# Display.net
KiCad netlist of a schematic drawn in Altium Designer
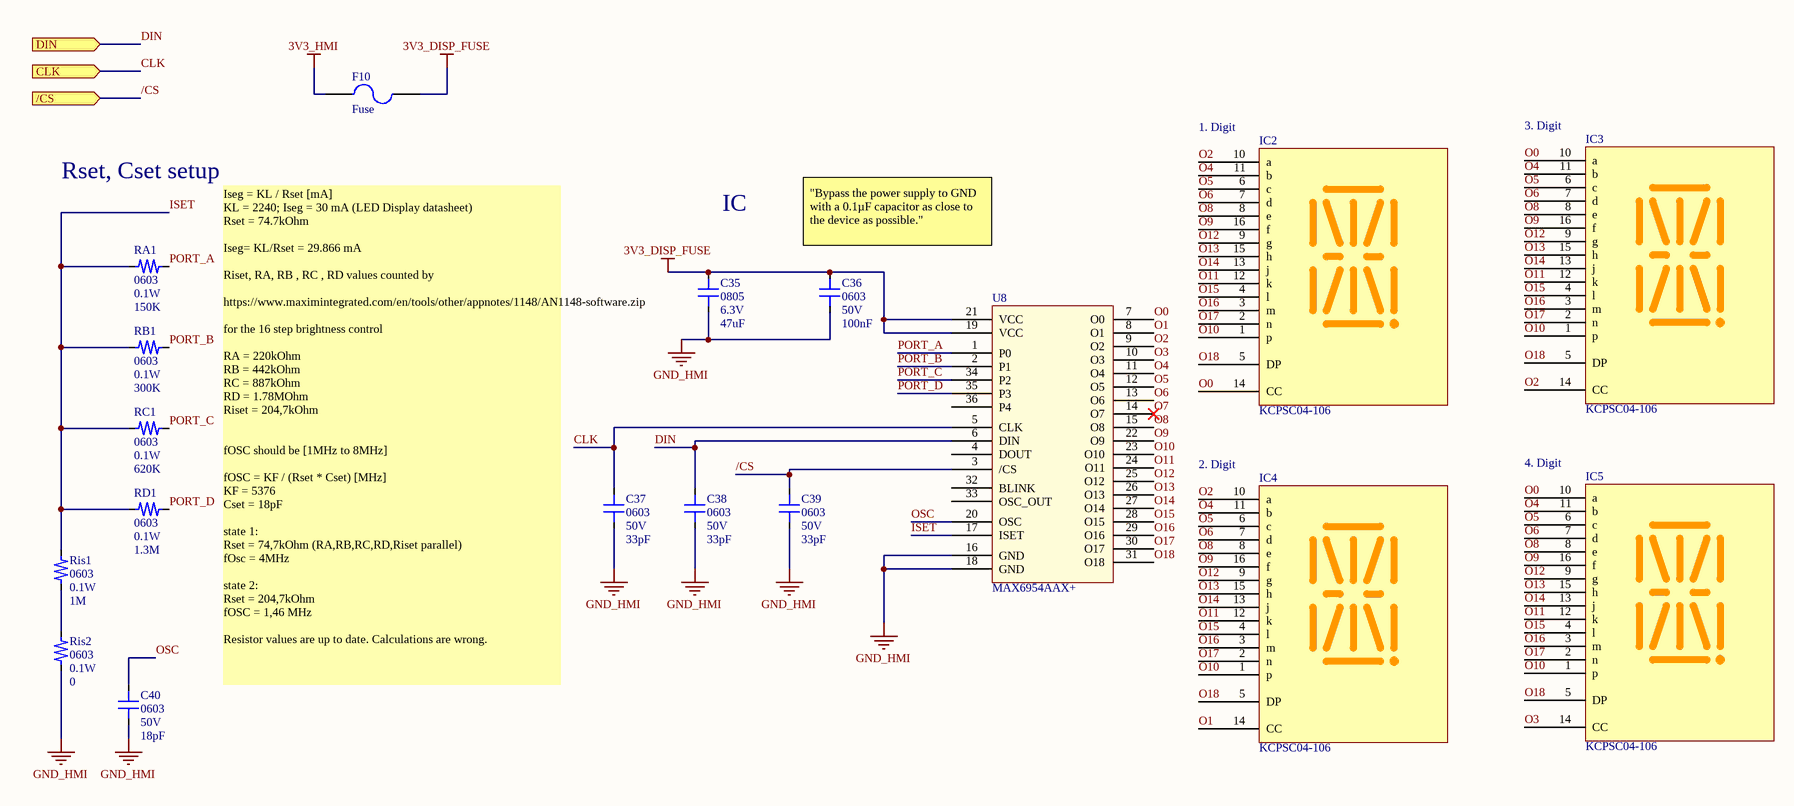
[diagram p0: Display.SchDoc]

(export (version "E")
  (design (tool "Eeschema 10.0.6"))
  (components
    (comp (ref "C35")
      (value "0805")
      (footprint "Components:C_0805")
      (fields
        (field (name "TOLERANCE") "20%")
        (field (name "PART NUMBER") "CL21A476MQYNNNE")
        (field (name "RATING") "6.3V")
        (field (name "ALTIUM_VALUE") "47uF")
      )
      (libsource (lib "Components") (part "Capacitor_Chip"))
    )
    (comp (ref "C36")
      (value "0603")
      (footprint "Components:C_0603")
      (fields
        (field (name "TOLERANCE") "10%")
        (field (name "PART NUMBER") "CC0603KRX7R9BB104")
        (field (name "RATING") "50V")
        (field (name "ALTIUM_VALUE") "100nF")
        (field (name "NI PART NUMBER") "716340-01")
      )
      (libsource (lib "Components") (part "Capacitor_Chip"))
    )
    (comp (ref "C37")
      (value "0603")
      (footprint "Components:C_0603")
      (fields
        (field (name "TOLERANCE") "5%")
        (field (name "PART NUMBER") "CL10C330JB8NNNC")
        (field (name "RATING") "50V")
        (field (name "ALTIUM_VALUE") "33pF")
        (field (name "NI PART NUMBER") "715511-01")
      )
      (libsource (lib "Components") (part "Capacitor_Chip"))
    )
    (comp (ref "C38")
      (value "0603")
      (footprint "Components:C_0603")
      (fields
        (field (name "TOLERANCE") "5%")
        (field (name "PART NUMBER") "CL10C330JB8NNNC")
        (field (name "RATING") "50V")
        (field (name "ALTIUM_VALUE") "33pF")
        (field (name "NI PART NUMBER") "715511-01")
      )
      (libsource (lib "Components") (part "Capacitor_Chip"))
    )
    (comp (ref "C39")
      (value "0603")
      (footprint "Components:C_0603")
      (fields
        (field (name "TOLERANCE") "5%")
        (field (name "PART NUMBER") "CL10C330JB8NNNC")
        (field (name "RATING") "50V")
        (field (name "ALTIUM_VALUE") "33pF")
        (field (name "NI PART NUMBER") "715511-01")
      )
      (libsource (lib "Components") (part "Capacitor_Chip"))
    )
    (comp (ref "C40")
      (value "0603")
      (footprint "Components:C_0603")
      (fields
        (field (name "TOLERANCE") "5%")
        (field (name "PART NUMBER") "CL10C180JB8NNNC")
        (field (name "RATING") "50V")
        (field (name "ALTIUM_VALUE") "18pF")
        (field (name "NI PART NUMBER") "715742-01")
      )
      (libsource (lib "Components") (part "Capacitor_Chip"))
    )
    (comp (ref "F10")
      (value "Fuse")
      (footprint "Components:F_0603")
      (fields (field (name "PART NUMBER") "0438001.WR") (field (name "NI PART NUMBER") "766308-01"))
      (libsource (lib "Components") (part "Fuse"))
    )
    (comp (ref "IC2")
      (value "KCPSC04-106")
      (footprint "Components:KCPSC04-106")
      (description "14SegmentDisplaySingle")
      (libsource (lib "KCPDC04_106") (part "14SegmentDisplaySingle"))
    )
    (comp (ref "IC3")
      (value "KCPSC04-106")
      (footprint "Components:KCPSC04-106")
      (description "14SegmentDisplaySingle")
      (libsource (lib "KCPDC04_106") (part "14SegmentDisplaySingle"))
    )
    (comp (ref "IC4")
      (value "KCPSC04-106")
      (footprint "Components:KCPSC04-106")
      (description "14SegmentDisplaySingle")
      (libsource (lib "KCPDC04_106") (part "14SegmentDisplaySingle"))
    )
    (comp (ref "IC5")
      (value "KCPSC04-106")
      (footprint "Components:KCPSC04-106")
      (description "14SegmentDisplaySingle")
      (libsource (lib "KCPDC04_106") (part "14SegmentDisplaySingle"))
    )
    (comp (ref "RA1")
      (value "0603")
      (footprint "Components:R_0603")
      (fields
        (field (name "TOLERANCE") "1%")
        (field (name "PART NUMBER") "CR-03FL7--220K")
        (field (name "RATING") "0.1W")
        (field (name "ALTIUM_VALUE") "150K")
        (field (name "NI PART NUMBER") "612705-01")
      )
      (libsource (lib "Components") (part "Resistor_Chip"))
    )
    (comp (ref "RB1")
      (value "0603")
      (footprint "Components:R_0603")
      (fields
        (field (name "TOLERANCE") "1%")
        (field (name "PART NUMBER") "CR-03FL7--220K")
        (field (name "RATING") "0.1W")
        (field (name "ALTIUM_VALUE") "300K")
        (field (name "NI PART NUMBER") "612705-01")
      )
      (libsource (lib "Components") (part "Resistor_Chip"))
    )
    (comp (ref "RC1")
      (value "0603")
      (footprint "Components:R_0603")
      (fields
        (field (name "TOLERANCE") "1%")
        (field (name "PART NUMBER") "CR-03FL7--220K")
        (field (name "RATING") "0.1W")
        (field (name "ALTIUM_VALUE") "620K")
        (field (name "NI PART NUMBER") "612705-01")
      )
      (libsource (lib "Components") (part "Resistor_Chip"))
    )
    (comp (ref "RD1")
      (value "0603")
      (footprint "Components:R_0603")
      (fields
        (field (name "TOLERANCE") "1%")
        (field (name "PART NUMBER") "CR-03FL7--220K")
        (field (name "RATING") "0.1W")
        (field (name "ALTIUM_VALUE") "1.3M")
        (field (name "NI PART NUMBER") "612705-01")
      )
      (libsource (lib "Components") (part "Resistor_Chip"))
    )
    (comp (ref "Ris1")
      (value "0603")
      (footprint "Components:R_0603")
      (fields
        (field (name "TOLERANCE") "1%")
        (field (name "PART NUMBER") "CR-03FL7---4K7")
        (field (name "RATING") "0.1W")
        (field (name "ALTIUM_VALUE") "1M")
        (field (name "NI PART NUMBER") "713782-01")
      )
      (libsource (lib "") (part "Resistor_Chip_1"))
    )
    (comp (ref "Ris2")
      (value "0603")
      (footprint "Components:R_0603")
      (fields
        (field (name "TOLERANCE") "1%")
        (field (name "PART NUMBER") "CR-03FL7--200K")
        (field (name "RATING") "0.1W")
        (field (name "ALTIUM_VALUE") "0")
        (field (name "NI PART NUMBER") "713614-01")
      )
      (libsource (lib "") (part "Resistor_Chip_1"))
    )
    (comp (ref "U8")
      (value "MAX6954AAX+")
      (footprint "Components:TSSOP-36")
      (description "16 Segment LED Driver")
      (libsource (lib "Components") (part "MAX6954"))
    )
  )
  (nets
    (net (code "1") (name "/CLK") (class "Default")
      (node (ref "C37") (pin "2") (pinfunction "C2_2") (pintype "passive"))
      (node (ref "U8") (pin "5") (pinfunction "CLK_5") (pintype "passive"))
    )
    (net (code "2") (name "/DIN") (class "Default")
      (node (ref "C38") (pin "2") (pinfunction "C2_2") (pintype "passive"))
      (node (ref "U8") (pin "6") (pinfunction "DIN_6") (pintype "passive"))
    )
    (net (code "3") (name "/ISET") (class "Default")
      (node (ref "RA1") (pin "2") (pinfunction "R2_2") (pintype "passive"))
      (node (ref "RB1") (pin "2") (pinfunction "R2_2") (pintype "passive"))
      (node (ref "RC1") (pin "2") (pinfunction "R2_2") (pintype "passive"))
      (node (ref "RD1") (pin "2") (pinfunction "R2_2") (pintype "passive"))
      (node (ref "Ris1") (pin "2") (pinfunction "R2_2") (pintype "passive"))
      (node (ref "U8") (pin "17") (pinfunction "ISET_17") (pintype "passive"))
    )
    (net (code "4") (name "/O0") (class "Default")
      (node (ref "IC2") (pin "14") (pinfunction "CC_14") (pintype "passive"))
      (node (ref "IC3") (pin "10") (pinfunction "a_10") (pintype "passive"))
      (node (ref "IC5") (pin "10") (pinfunction "a_10") (pintype "passive"))
      (node (ref "U8") (pin "7") (pinfunction "O0_7") (pintype "passive"))
    )
    (net (code "5") (name "/O1") (class "Default")
      (node (ref "IC4") (pin "14") (pinfunction "CC_14") (pintype "passive"))
      (node (ref "U8") (pin "8") (pinfunction "O1_8") (pintype "passive"))
    )
    (net (code "6") (name "/O2") (class "Default")
      (node (ref "IC2") (pin "10") (pinfunction "a_10") (pintype "passive"))
      (node (ref "IC3") (pin "14") (pinfunction "CC_14") (pintype "passive"))
      (node (ref "IC4") (pin "10") (pinfunction "a_10") (pintype "passive"))
      (node (ref "U8") (pin "9") (pinfunction "O2_9") (pintype "passive"))
    )
    (net (code "7") (name "/O3") (class "Default")
      (node (ref "IC5") (pin "14") (pinfunction "CC_14") (pintype "passive"))
      (node (ref "U8") (pin "10") (pinfunction "O3_10") (pintype "passive"))
    )
    (net (code "8") (name "/O4") (class "Default")
      (node (ref "IC2") (pin "11") (pinfunction "b_11") (pintype "passive"))
      (node (ref "IC3") (pin "11") (pinfunction "b_11") (pintype "passive"))
      (node (ref "IC4") (pin "11") (pinfunction "b_11") (pintype "passive"))
      (node (ref "IC5") (pin "11") (pinfunction "b_11") (pintype "passive"))
      (node (ref "U8") (pin "11") (pinfunction "O4_11") (pintype "passive"))
    )
    (net (code "9") (name "/O5") (class "Default")
      (node (ref "IC2") (pin "6") (pinfunction "c_6") (pintype "passive"))
      (node (ref "IC3") (pin "6") (pinfunction "c_6") (pintype "passive"))
      (node (ref "IC4") (pin "6") (pinfunction "c_6") (pintype "passive"))
      (node (ref "IC5") (pin "6") (pinfunction "c_6") (pintype "passive"))
      (node (ref "U8") (pin "12") (pinfunction "O5_12") (pintype "passive"))
    )
    (net (code "10") (name "/O6") (class "Default")
      (node (ref "IC2") (pin "7") (pinfunction "d_7") (pintype "passive"))
      (node (ref "IC3") (pin "7") (pinfunction "d_7") (pintype "passive"))
      (node (ref "IC4") (pin "7") (pinfunction "d_7") (pintype "passive"))
      (node (ref "IC5") (pin "7") (pinfunction "d_7") (pintype "passive"))
      (node (ref "U8") (pin "13") (pinfunction "O6_13") (pintype "passive"))
    )
    (net (code "11") (name "/O7") (class "Default")
      (node (ref "U8") (pin "14") (pinfunction "O7_14") (pintype "passive+no_connect"))
    )
    (net (code "12") (name "/O8") (class "Default")
      (node (ref "IC2") (pin "8") (pinfunction "e_8") (pintype "passive"))
      (node (ref "IC3") (pin "8") (pinfunction "e_8") (pintype "passive"))
      (node (ref "IC4") (pin "8") (pinfunction "e_8") (pintype "passive"))
      (node (ref "IC5") (pin "8") (pinfunction "e_8") (pintype "passive"))
      (node (ref "U8") (pin "15") (pinfunction "O8_15") (pintype "passive"))
    )
    (net (code "13") (name "/O9") (class "Default")
      (node (ref "IC2") (pin "16") (pinfunction "f_16") (pintype "passive"))
      (node (ref "IC3") (pin "16") (pinfunction "f_16") (pintype "passive"))
      (node (ref "IC4") (pin "16") (pinfunction "f_16") (pintype "passive"))
      (node (ref "IC5") (pin "16") (pinfunction "f_16") (pintype "passive"))
      (node (ref "U8") (pin "22") (pinfunction "O9_22") (pintype "passive"))
    )
    (net (code "14") (name "/O10") (class "Default")
      (node (ref "IC2") (pin "1") (pinfunction "p_1") (pintype "passive"))
      (node (ref "IC3") (pin "1") (pinfunction "p_1") (pintype "passive"))
      (node (ref "IC4") (pin "1") (pinfunction "p_1") (pintype "passive"))
      (node (ref "IC5") (pin "1") (pinfunction "p_1") (pintype "passive"))
      (node (ref "U8") (pin "23") (pinfunction "O10_23") (pintype "passive"))
    )
    (net (code "15") (name "/O11") (class "Default")
      (node (ref "IC2") (pin "12") (pinfunction "k_12") (pintype "passive"))
      (node (ref "IC3") (pin "12") (pinfunction "k_12") (pintype "passive"))
      (node (ref "IC4") (pin "12") (pinfunction "k_12") (pintype "passive"))
      (node (ref "IC5") (pin "12") (pinfunction "k_12") (pintype "passive"))
      (node (ref "U8") (pin "24") (pinfunction "O11_24") (pintype "passive"))
    )
    (net (code "16") (name "/O12") (class "Default")
      (node (ref "IC2") (pin "9") (pinfunction "g_9") (pintype "passive"))
      (node (ref "IC3") (pin "9") (pinfunction "g_9") (pintype "passive"))
      (node (ref "IC4") (pin "9") (pinfunction "g_9") (pintype "passive"))
      (node (ref "IC5") (pin "9") (pinfunction "g_9") (pintype "passive"))
      (node (ref "U8") (pin "25") (pinfunction "O12_25") (pintype "passive"))
    )
    (net (code "17") (name "/O13") (class "Default")
      (node (ref "IC2") (pin "15") (pinfunction "h_15") (pintype "passive"))
      (node (ref "IC3") (pin "15") (pinfunction "h_15") (pintype "passive"))
      (node (ref "IC4") (pin "15") (pinfunction "h_15") (pintype "passive"))
      (node (ref "IC5") (pin "15") (pinfunction "h_15") (pintype "passive"))
      (node (ref "U8") (pin "26") (pinfunction "O13_26") (pintype "passive"))
    )
    (net (code "18") (name "/O14") (class "Default")
      (node (ref "IC2") (pin "13") (pinfunction "j_13") (pintype "passive"))
      (node (ref "IC3") (pin "13") (pinfunction "j_13") (pintype "passive"))
      (node (ref "IC4") (pin "13") (pinfunction "j_13") (pintype "passive"))
      (node (ref "IC5") (pin "13") (pinfunction "j_13") (pintype "passive"))
      (node (ref "U8") (pin "27") (pinfunction "O14_27") (pintype "passive"))
    )
    (net (code "19") (name "/O15") (class "Default")
      (node (ref "IC2") (pin "4") (pinfunction "l_4") (pintype "passive"))
      (node (ref "IC3") (pin "4") (pinfunction "l_4") (pintype "passive"))
      (node (ref "IC4") (pin "4") (pinfunction "l_4") (pintype "passive"))
      (node (ref "IC5") (pin "4") (pinfunction "l_4") (pintype "passive"))
      (node (ref "U8") (pin "28") (pinfunction "O15_28") (pintype "passive"))
    )
    (net (code "20") (name "/O16") (class "Default")
      (node (ref "IC2") (pin "3") (pinfunction "m_3") (pintype "passive"))
      (node (ref "IC3") (pin "3") (pinfunction "m_3") (pintype "passive"))
      (node (ref "IC4") (pin "3") (pinfunction "m_3") (pintype "passive"))
      (node (ref "IC5") (pin "3") (pinfunction "m_3") (pintype "passive"))
      (node (ref "U8") (pin "29") (pinfunction "O16_29") (pintype "passive"))
    )
    (net (code "21") (name "/O17") (class "Default")
      (node (ref "IC2") (pin "2") (pinfunction "n_2") (pintype "passive"))
      (node (ref "IC3") (pin "2") (pinfunction "n_2") (pintype "passive"))
      (node (ref "IC4") (pin "2") (pinfunction "n_2") (pintype "passive"))
      (node (ref "IC5") (pin "2") (pinfunction "n_2") (pintype "passive"))
      (node (ref "U8") (pin "30") (pinfunction "O17_30") (pintype "passive"))
    )
    (net (code "22") (name "/O18") (class "Default")
      (node (ref "IC2") (pin "5") (pinfunction "DP_5") (pintype "passive"))
      (node (ref "IC3") (pin "5") (pinfunction "DP_5") (pintype "passive"))
      (node (ref "IC4") (pin "5") (pinfunction "DP_5") (pintype "passive"))
      (node (ref "IC5") (pin "5") (pinfunction "DP_5") (pintype "passive"))
      (node (ref "U8") (pin "31") (pinfunction "O18_31") (pintype "passive"))
    )
    (net (code "23") (name "/OSC") (class "Default")
      (node (ref "C40") (pin "2") (pinfunction "C2_2") (pintype "passive"))
      (node (ref "U8") (pin "20") (pinfunction "OSC_20") (pintype "passive"))
    )
    (net (code "24") (name "/PORT_A") (class "Default")
      (node (ref "RA1") (pin "1") (pinfunction "R1_1") (pintype "passive"))
      (node (ref "U8") (pin "1") (pinfunction "P0_1") (pintype "passive"))
    )
    (net (code "25") (name "/PORT_B") (class "Default")
      (node (ref "RB1") (pin "1") (pinfunction "R1_1") (pintype "passive"))
      (node (ref "U8") (pin "2") (pinfunction "P1_2") (pintype "passive"))
    )
    (net (code "26") (name "/PORT_C") (class "Default")
      (node (ref "RC1") (pin "1") (pinfunction "R1_1") (pintype "passive"))
      (node (ref "U8") (pin "34") (pinfunction "P2_34") (pintype "passive"))
    )
    (net (code "27") (name "/PORT_D") (class "Default")
      (node (ref "RD1") (pin "1") (pinfunction "R1_1") (pintype "passive"))
      (node (ref "U8") (pin "35") (pinfunction "P3_35") (pintype "passive"))
    )
    (net (code "28") (name "/{slash}CS") (class "Default")
      (node (ref "C39") (pin "2") (pinfunction "C2_2") (pintype "passive"))
      (node (ref "U8") (pin "3") (pinfunction "/CS_3") (pintype "passive"))
    )
    (net (code "29") (name "3V3_DISP_FUSE") (class "Default")
      (node (ref "C35") (pin "2") (pinfunction "C2_2") (pintype "passive"))
      (node (ref "C36") (pin "2") (pinfunction "C2_2") (pintype "passive"))
      (node (ref "F10") (pin "2") (pinfunction "2_2") (pintype "passive"))
      (node (ref "U8") (pin "19") (pinfunction "VCC_19") (pintype "passive"))
      (node (ref "U8") (pin "21") (pinfunction "VCC_21") (pintype "passive"))
    )
    (net (code "30") (name "3V3_HMI") (class "Default")
      (node (ref "F10") (pin "1") (pinfunction "1_1") (pintype "passive"))
    )
    (net (code "31") (name "GND_HMI") (class "Default")
      (node (ref "C35") (pin "1") (pinfunction "C1_1") (pintype "passive"))
      (node (ref "C36") (pin "1") (pinfunction "C1_1") (pintype "passive"))
      (node (ref "C37") (pin "1") (pinfunction "C1_1") (pintype "passive"))
      (node (ref "C38") (pin "1") (pinfunction "C1_1") (pintype "passive"))
      (node (ref "C39") (pin "1") (pinfunction "C1_1") (pintype "passive"))
      (node (ref "C40") (pin "1") (pinfunction "C1_1") (pintype "passive"))
      (node (ref "Ris2") (pin "1") (pinfunction "R1_1") (pintype "passive"))
      (node (ref "U8") (pin "16") (pinfunction "GND_16") (pintype "passive"))
      (node (ref "U8") (pin "18") (pinfunction "GND_18") (pintype "passive"))
    )
    (net (code "32") (name "Net-(Ris1-R1)") (class "Default")
      (node (ref "Ris1") (pin "1") (pinfunction "R1_1") (pintype "passive"))
      (node (ref "Ris2") (pin "2") (pinfunction "R2_2") (pintype "passive"))
    )
    (net (code "33") (name "unconnected-(U8-BLINK-Pad32)") (class "Default")
      (node (ref "U8") (pin "32") (pinfunction "BLINK_32") (pintype "passive"))
    )
    (net (code "34") (name "unconnected-(U8-DOUT-Pad4)") (class "Default")
      (node (ref "U8") (pin "4") (pinfunction "DOUT_4") (pintype "passive"))
    )
    (net (code "35") (name "unconnected-(U8-OSC_OUT-Pad33)") (class "Default")
      (node (ref "U8") (pin "33") (pinfunction "OSC_OUT_33") (pintype "passive"))
    )
    (net (code "36") (name "unconnected-(U8-P4-Pad36)") (class "Default")
      (node (ref "U8") (pin "36") (pinfunction "P4_36") (pintype "passive"))
    )
  )
)
